# LM_001.net
KiCad netlist of a schematic drawn in Altium Designer
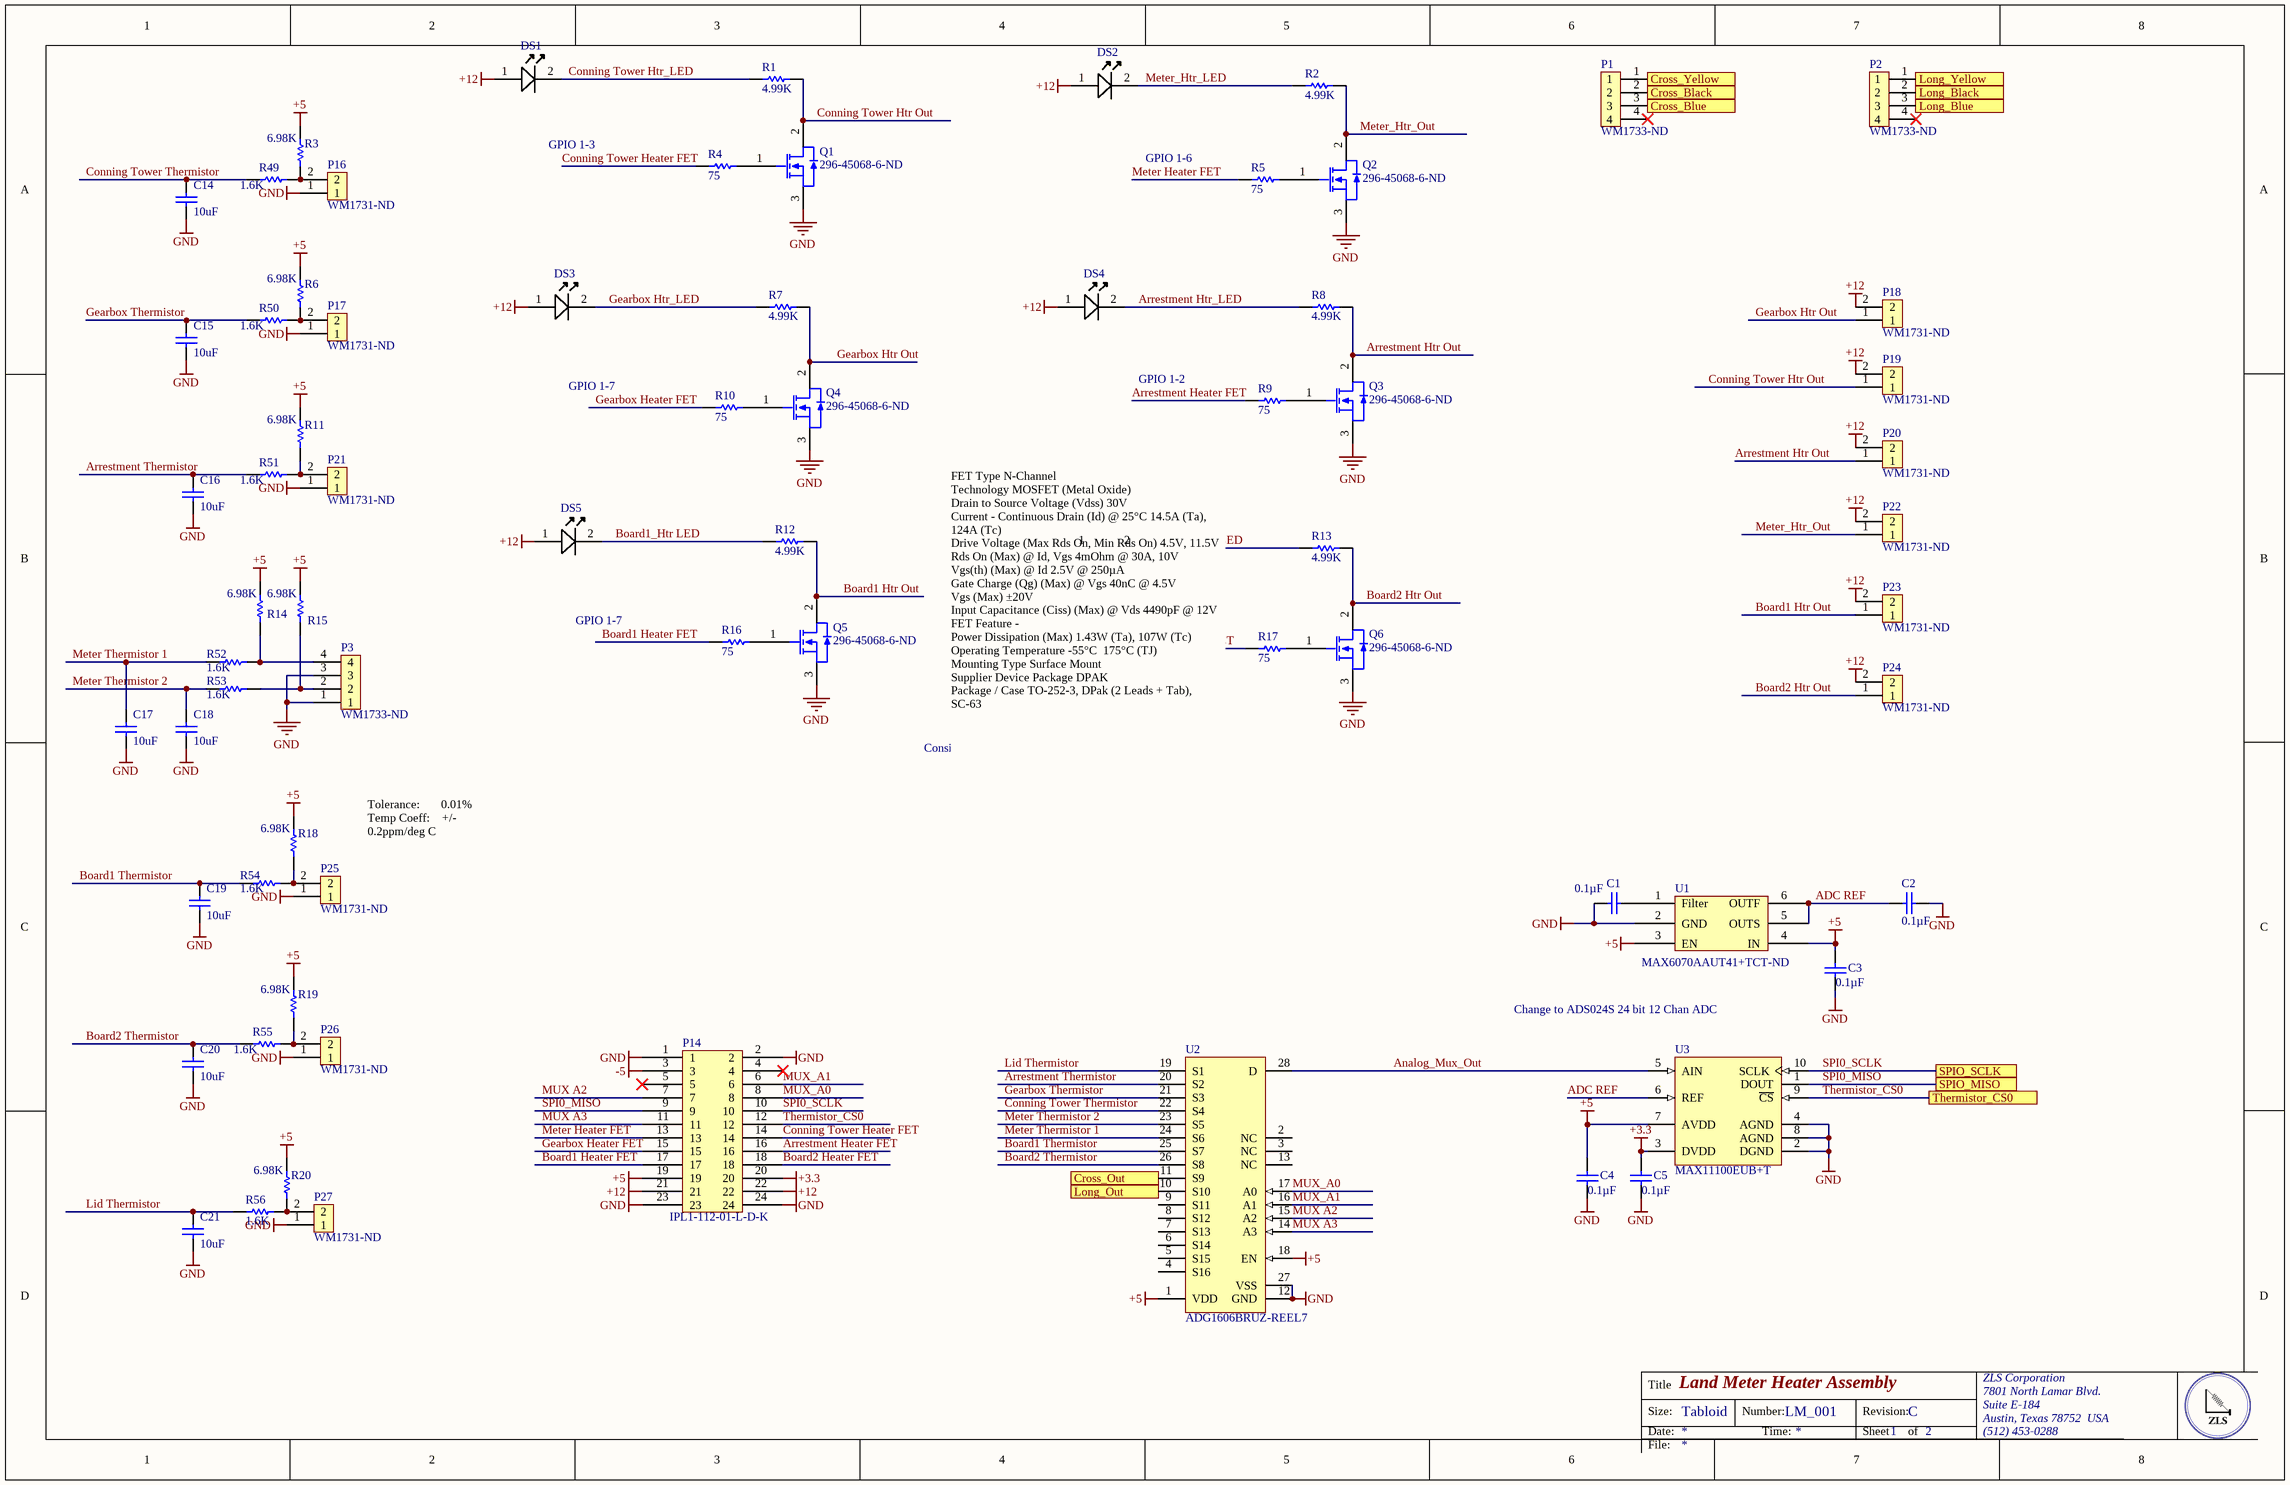
[diagram p0: LM_001.SchDoc]

(export (version "E")
  (design (tool "Eeschema 10.0.6"))
  (components
    (comp (ref "C1")
      (value "CAP CER 0.1UF 25V X7R 0805")
      (footprint "CAPC0805(2012)145_N")
      (fields
        (field (name "MANUFACTURER") "Murata Electronics North America")
        (field (name "MANUFACTURER PART NUMBER") "GRM21BR71E104KA01L")
        (field (name "CAPACITANCE") "0.1µF")
        (field (name "TOLERANCE") "±10%")
      )
      (libsource (lib "Altium Content Vault") (part "CMP-1036-04795-1"))
    )
    (comp (ref "C2")
      (value "CAP CER 0.1UF 25V X7R 0805")
      (footprint "CAPC0805(2012)145_N")
      (fields
        (field (name "MANUFACTURER") "Murata Electronics North America")
        (field (name "MANUFACTURER PART NUMBER") "GRM21BR71E104KA01L")
        (field (name "CAPACITANCE") "0.1µF")
        (field (name "TOLERANCE") "±10%")
      )
      (libsource (lib "Altium Content Vault") (part "CMP-1036-04795-1"))
    )
    (comp (ref "C3")
      (value "CAP CER 0.1UF 25V X7R 0805")
      (footprint "CAPC0805(2012)145_N")
      (fields
        (field (name "MANUFACTURER") "Murata Electronics North America")
        (field (name "MANUFACTURER PART NUMBER") "GRM21BR71E104KA01L")
        (field (name "CAPACITANCE") "0.1µF")
        (field (name "TOLERANCE") "±10%")
      )
      (libsource (lib "Altium Content Vault") (part "CMP-1036-04795-1"))
    )
    (comp (ref "C4")
      (value "CAP CER 0.1UF 25V X7R 0805")
      (footprint "CAPC0805(2012)145_N")
      (fields
        (field (name "MANUFACTURER") "Murata Electronics North America")
        (field (name "MANUFACTURER PART NUMBER") "GRM21BR71E104KA01L")
        (field (name "CAPACITANCE") "0.1µF")
        (field (name "TOLERANCE") "±10%")
      )
      (libsource (lib "Altium Content Vault") (part "CMP-1036-04795-1"))
    )
    (comp (ref "C5")
      (value "CAP CER 0.1UF 25V X7R 0805")
      (footprint "CAPC0805(2012)145_N")
      (fields
        (field (name "MANUFACTURER") "Murata Electronics North America")
        (field (name "MANUFACTURER PART NUMBER") "GRM21BR71E104KA01L")
        (field (name "CAPACITANCE") "0.1µF")
        (field (name "TOLERANCE") "±10%")
      )
      (libsource (lib "Altium Content Vault") (part "CMP-1036-04795-1"))
    )
    (comp (ref "C14")
      (value "10uF")
      (footprint "CAPC0805(2012)145_N")
      (description "CAP CER 10UF 16V X6S 0805")
      (fields
        (field (name "MANUFACTURER") "TDK Corporation")
        (field (name "MANUFACTURER PART NUMBER") "C2012X6S1C106K085AC")
      )
      (libsource (lib "Altium Content Vault") (part "CMP-1036-04795-1"))
    )
    (comp (ref "C15")
      (value "10uF")
      (footprint "CAPC0805(2012)145_N")
      (description "CAP CER 10UF 16V X6S 0805")
      (fields
        (field (name "MANUFACTURER") "TDK Corporation")
        (field (name "MANUFACTURER PART NUMBER") "C2012X6S1C106K085AC")
      )
      (libsource (lib "Altium Content Vault") (part "CMP-1036-04795-1"))
    )
    (comp (ref "C16")
      (value "10uF")
      (footprint "CAPC0805(2012)145_N")
      (description "CAP CER 10UF 16V X6S 0805")
      (fields
        (field (name "MANUFACTURER") "TDK Corporation")
        (field (name "MANUFACTURER PART NUMBER") "C2012X6S1C106K085AC")
      )
      (libsource (lib "Altium Content Vault") (part "CMP-1036-04795-1"))
    )
    (comp (ref "C17")
      (value "10uF")
      (footprint "CAPC0805(2012)145_N")
      (description "CAP CER 10UF 16V X6S 0805")
      (fields
        (field (name "MANUFACTURER") "TDK Corporation")
        (field (name "MANUFACTURER PART NUMBER") "C2012X6S1C106K085AC")
      )
      (libsource (lib "Altium Content Vault") (part "CMP-1036-04795-1"))
    )
    (comp (ref "C18")
      (value "10uF")
      (footprint "CAPC0805(2012)145_N")
      (description "CAP CER 10UF 16V X6S 0805")
      (fields
        (field (name "MANUFACTURER") "TDK Corporation")
        (field (name "MANUFACTURER PART NUMBER") "C2012X6S1C106K085AC")
      )
      (libsource (lib "Altium Content Vault") (part "CMP-1036-04795-1"))
    )
    (comp (ref "C19")
      (value "10uF")
      (footprint "CAPC0805(2012)145_N")
      (description "CAP CER 10UF 16V X6S 0805")
      (fields
        (field (name "MANUFACTURER") "TDK Corporation")
        (field (name "MANUFACTURER PART NUMBER") "C2012X6S1C106K085AC")
      )
      (libsource (lib "Altium Content Vault") (part "CMP-1036-04795-1"))
    )
    (comp (ref "C20")
      (value "10uF")
      (footprint "CAPC0805(2012)145_N")
      (description "CAP CER 10UF 16V X6S 0805")
      (fields
        (field (name "MANUFACTURER") "TDK Corporation")
        (field (name "MANUFACTURER PART NUMBER") "C2012X6S1C106K085AC")
      )
      (libsource (lib "Altium Content Vault") (part "CMP-1036-04795-1"))
    )
    (comp (ref "C21")
      (value "10uF")
      (footprint "CAPC0805(2012)145_N")
      (description "CAP CER 10UF 16V X6S 0805")
      (fields
        (field (name "MANUFACTURER") "TDK Corporation")
        (field (name "MANUFACTURER PART NUMBER") "C2012X6S1C106K085AC")
      )
      (libsource (lib "Altium Content Vault") (part "CMP-1036-04795-1"))
    )
    (comp (ref "DS1")
      (value "LTST-S220KRKT")
      (footprint "0805C_L")
      (description "LED RED CLEAR CHIP SMD R/A")
      (fields (field (name "MANUFACTURER") "Vishay / Lite-On"))
      (libsource (lib "*") (part "LED A/K"))
    )
    (comp (ref "DS2")
      (value "LTST-S220KRKT")
      (footprint "0805C_L")
      (description "LED RED CLEAR CHIP SMD R/A")
      (fields (field (name "MANUFACTURER") "Vishay / Lite-On"))
      (libsource (lib "*") (part "LED A/K"))
    )
    (comp (ref "DS3")
      (value "LTST-S220KRKT")
      (footprint "0805C_L")
      (description "LED RED CLEAR CHIP SMD R/A")
      (fields (field (name "MANUFACTURER") "Vishay / Lite-On"))
      (libsource (lib "*") (part "LED A/K"))
    )
    (comp (ref "DS4")
      (value "LTST-S220KRKT")
      (footprint "0805C_L")
      (description "LED RED CLEAR CHIP SMD R/A")
      (fields (field (name "MANUFACTURER") "Vishay / Lite-On"))
      (libsource (lib "*") (part "LED A/K"))
    )
    (comp (ref "DS5")
      (value "LTST-S220KRKT")
      (footprint "0805C_L")
      (description "LED RED CLEAR CHIP SMD R/A")
      (fields (field (name "MANUFACTURER") "Vishay / Lite-On"))
      (libsource (lib "*") (part "LED A/K"))
    )
    (comp (ref "DS6")
      (value "LTST-S220KRKT")
      (footprint "0805C_L")
      (description "LED RED CLEAR CHIP SMD R/A")
      (fields (field (name "MANUFACTURER") "Vishay / Lite-On"))
      (libsource (lib "*") (part "LED A/K"))
    )
    (comp (ref "P1")
      (value "0530470410")
      (footprint "0530470410")
      (description "Conn Wire to Board HDR 4 POS 1.25mm Solder ST Thru-Hole PicoBlade™ Tray")
      (fields (field (name "SUPPLIER PART NUMBER 1") "WM1733-ND") (field (name "MANUFACTURER") "Molex"))
      (libsource (lib "ZLS_Schematic_lib") (part "0530470410"))
    )
    (comp (ref "P2")
      (value "0530470410")
      (footprint "0530470410")
      (description "Conn Wire to Board HDR 4 POS 1.25mm Solder ST Thru-Hole PicoBlade™ Tray")
      (fields (field (name "SUPPLIER PART NUMBER 1") "WM1733-ND") (field (name "MANUFACTURER") "Molex"))
      (libsource (lib "ZLS_Schematic_lib") (part "0530470410"))
    )
    (comp (ref "P3")
      (value "0530470410")
      (footprint "0530470410")
      (description "Conn Wire to Board HDR 4 POS 1.25mm Solder ST Thru-Hole PicoBlade™ Tray")
      (fields (field (name "SUPPLIER PART NUMBER 1") "WM1733-ND") (field (name "MANUFACTURER") "Molex"))
      (libsource (lib "") (part "0530470410_1"))
    )
    (comp (ref "P14")
      (value "IPL1-112-01-L-D-K")
      (footprint "IPL1-112-01-F-S-K")
      (fields (field (name "MANUFACTURER") "Samtec Inc."))
      (libsource (lib "ZLS_Schematic_lib") (part "IPL1-112-01-F-S-K"))
    )
    (comp (ref "P16")
      (value "0530470210")
      (footprint "0530470210")
      (description "Conn Shrouded Header HDR 2 POS 1.25mm Solder ST Thru-Hole PicoBlade™ Tray")
      (fields (field (name "SUPPLIER PART NUMBER 1") "WM1731-ND") (field (name "MANUFACTURER") "Molex"))
      (libsource (lib "ZLS_Schematic_lib") (part "0530470210"))
    )
    (comp (ref "P17")
      (value "0530470210")
      (footprint "0530470210")
      (description "Conn Shrouded Header HDR 2 POS 1.25mm Solder ST Thru-Hole PicoBlade™ Tray")
      (fields (field (name "SUPPLIER PART NUMBER 1") "WM1731-ND") (field (name "MANUFACTURER") "Molex"))
      (libsource (lib "ZLS_Schematic_lib") (part "0530470210"))
    )
    (comp (ref "P18")
      (value "0530470210")
      (footprint "0530470210")
      (description "Conn Shrouded Header HDR 2 POS 1.25mm Solder ST Thru-Hole PicoBlade™ Tray")
      (fields (field (name "SUPPLIER PART NUMBER 1") "WM1731-ND") (field (name "MANUFACTURER") "Molex"))
      (libsource (lib "ZLS_Schematic_lib") (part "0530470210"))
    )
    (comp (ref "P19")
      (value "0530470210")
      (footprint "0530470210")
      (description "Conn Shrouded Header HDR 2 POS 1.25mm Solder ST Thru-Hole PicoBlade™ Tray")
      (fields (field (name "SUPPLIER PART NUMBER 1") "WM1731-ND") (field (name "MANUFACTURER") "Molex"))
      (libsource (lib "ZLS_Schematic_lib") (part "0530470210"))
    )
    (comp (ref "P20")
      (value "0530470210")
      (footprint "0530470210")
      (description "Conn Shrouded Header HDR 2 POS 1.25mm Solder ST Thru-Hole PicoBlade™ Tray")
      (fields (field (name "SUPPLIER PART NUMBER 1") "WM1731-ND") (field (name "MANUFACTURER") "Molex"))
      (libsource (lib "ZLS_Schematic_lib") (part "0530470210"))
    )
    (comp (ref "P21")
      (value "0530470210")
      (footprint "0530470210")
      (description "Conn Shrouded Header HDR 2 POS 1.25mm Solder ST Thru-Hole PicoBlade™ Tray")
      (fields (field (name "SUPPLIER PART NUMBER 1") "WM1731-ND") (field (name "MANUFACTURER") "Molex"))
      (libsource (lib "ZLS_Schematic_lib") (part "0530470210"))
    )
    (comp (ref "P22")
      (value "0530470210")
      (footprint "0530470210")
      (description "Conn Shrouded Header HDR 2 POS 1.25mm Solder ST Thru-Hole PicoBlade™ Tray")
      (fields (field (name "SUPPLIER PART NUMBER 1") "WM1731-ND") (field (name "MANUFACTURER") "Molex"))
      (libsource (lib "ZLS_Schematic_lib") (part "0530470210"))
    )
    (comp (ref "P23")
      (value "0530470210")
      (footprint "0530470210")
      (description "Conn Shrouded Header HDR 2 POS 1.25mm Solder ST Thru-Hole PicoBlade™ Tray")
      (fields (field (name "SUPPLIER PART NUMBER 1") "WM1731-ND") (field (name "MANUFACTURER") "Molex"))
      (libsource (lib "ZLS_Schematic_lib") (part "0530470210"))
    )
    (comp (ref "P24")
      (value "0530470210")
      (footprint "0530470210")
      (description "Conn Shrouded Header HDR 2 POS 1.25mm Solder ST Thru-Hole PicoBlade™ Tray")
      (fields (field (name "SUPPLIER PART NUMBER 1") "WM1731-ND") (field (name "MANUFACTURER") "Molex"))
      (libsource (lib "ZLS_Schematic_lib") (part "0530470210"))
    )
    (comp (ref "P25")
      (value "0530470210")
      (footprint "0530470210")
      (description "Conn Shrouded Header HDR 2 POS 1.25mm Solder ST Thru-Hole PicoBlade™ Tray")
      (fields (field (name "SUPPLIER PART NUMBER 1") "WM1731-ND") (field (name "MANUFACTURER") "Molex"))
      (libsource (lib "ZLS_Schematic_lib") (part "0530470210"))
    )
    (comp (ref "P26")
      (value "0530470210")
      (footprint "0530470210")
      (description "Conn Shrouded Header HDR 2 POS 1.25mm Solder ST Thru-Hole PicoBlade™ Tray")
      (fields (field (name "SUPPLIER PART NUMBER 1") "WM1731-ND") (field (name "MANUFACTURER") "Molex"))
      (libsource (lib "ZLS_Schematic_lib") (part "0530470210"))
    )
    (comp (ref "P27")
      (value "0530470210")
      (footprint "0530470210")
      (description "Conn Shrouded Header HDR 2 POS 1.25mm Solder ST Thru-Hole PicoBlade™ Tray")
      (fields (field (name "SUPPLIER PART NUMBER 1") "WM1731-ND") (field (name "MANUFACTURER") "Molex"))
      (libsource (lib "ZLS_Schematic_lib") (part "0530470210"))
    )
    (comp (ref "Q1")
      (value "CSD17585F5T")
      (footprint "CSD17585F5T")
      (description "MOSFET N-CH 30V 5.9A PICOSTAR")
      (fields (field (name "SUPPLIER PART NUMBER 1") "296-45068-6-ND"))
      (libsource (lib "ZLS_Schematic_lib") (part "CSD17585F5T"))
    )
    (comp (ref "Q2")
      (value "CSD17585F5T")
      (footprint "CSD17585F5T")
      (description "MOSFET N-CH 30V 5.9A PICOSTAR")
      (fields (field (name "SUPPLIER PART NUMBER 1") "296-45068-6-ND"))
      (libsource (lib "ZLS_Schematic_lib") (part "CSD17585F5T"))
    )
    (comp (ref "Q3")
      (value "CSD17585F5T")
      (footprint "CSD17585F5T")
      (description "MOSFET N-CH 30V 5.9A PICOSTAR")
      (fields (field (name "SUPPLIER PART NUMBER 1") "296-45068-6-ND"))
      (libsource (lib "ZLS_Schematic_lib") (part "CSD17585F5T"))
    )
    (comp (ref "Q4")
      (value "CSD17585F5T")
      (footprint "CSD17585F5T")
      (description "MOSFET N-CH 30V 5.9A PICOSTAR")
      (fields (field (name "SUPPLIER PART NUMBER 1") "296-45068-6-ND"))
      (libsource (lib "ZLS_Schematic_lib") (part "CSD17585F5T"))
    )
    (comp (ref "Q5")
      (value "CSD17585F5T")
      (footprint "CSD17585F5T")
      (description "MOSFET N-CH 30V 5.9A PICOSTAR")
      (fields (field (name "SUPPLIER PART NUMBER 1") "296-45068-6-ND"))
      (libsource (lib "ZLS_Schematic_lib") (part "CSD17585F5T"))
    )
    (comp (ref "Q6")
      (value "CSD17585F5T")
      (footprint "CSD17585F5T")
      (description "MOSFET N-CH 30V 5.9A PICOSTAR")
      (fields (field (name "SUPPLIER PART NUMBER 1") "296-45068-6-ND"))
      (libsource (lib "ZLS_Schematic_lib") (part "CSD17585F5T"))
    )
    (comp (ref "R1")
      (value "4.99K")
      (footprint "RESC0805(2012)_L")
      (description "RES SMD 4.99K OHM 1% 1/8W 0805")
      (fields
        (field (name "MANUFACTURER") "Vishay Dale")
        (field (name "MANUFACTURER PART NUMBER") "CRCW08054K99FKEA")
      )
      (libsource (lib "Altium Content Vault") (part "CMP-1013-00393-1"))
    )
    (comp (ref "R2")
      (value "4.99K")
      (footprint "RESC0805(2012)_L")
      (description "RES SMD 4.99K OHM 1% 1/8W 0805")
      (fields
        (field (name "MANUFACTURER") "Vishay Dale")
        (field (name "MANUFACTURER PART NUMBER") "CRCW08054K99FKEA")
      )
      (libsource (lib "Altium Content Vault") (part "CMP-1013-00393-1"))
    )
    (comp (ref "R3")
      (value "6.98K")
      (footprint "RESC0805(2012)_N")
      (description "RES SMD 6.98K OHM 1% 1/8W 0805")
      (fields
        (field (name "MANUFACTURER") "Vishay Dale")
        (field (name "MANUFACTURER PART NUMBER") "CRCW08056K98FKEA")
      )
      (libsource (lib "Altium Content Vault") (part "CMP-1013-00606-1"))
    )
    (comp (ref "R4")
      (value "75")
      (footprint "RESC0805(2012)_L")
      (description "RES SMD 75 OHM 1% 1/8W 0805")
      (fields
        (field (name "MANUFACTURER") "Vishay Dale")
        (field (name "MANUFACTURER PART NUMBER") "CRCW080575R0FKTA")
      )
      (libsource (lib "Altium Content Vault") (part "CMP-1013-00393-1"))
    )
    (comp (ref "R5")
      (value "75")
      (footprint "RESC0805(2012)_L")
      (description "RES SMD 75 OHM 1% 1/8W 0805")
      (fields
        (field (name "MANUFACTURER") "Vishay Dale")
        (field (name "MANUFACTURER PART NUMBER") "CRCW080575R0FKTA")
      )
      (libsource (lib "Altium Content Vault") (part "CMP-1013-00393-1"))
    )
    (comp (ref "R6")
      (value "6.98K")
      (footprint "RESC0805(2012)_N")
      (description "RES SMD 6.98K OHM 1% 1/8W 0805")
      (fields
        (field (name "MANUFACTURER") "Vishay Dale")
        (field (name "MANUFACTURER PART NUMBER") "CRCW08056K98FKEA")
      )
      (libsource (lib "Altium Content Vault") (part "CMP-1013-00606-1"))
    )
    (comp (ref "R7")
      (value "4.99K")
      (footprint "RESC0805(2012)_L")
      (description "RES SMD 4.99K OHM 1% 1/8W 0805")
      (fields
        (field (name "MANUFACTURER") "Vishay Dale")
        (field (name "MANUFACTURER PART NUMBER") "CRCW08054K99FKEA")
      )
      (libsource (lib "Altium Content Vault") (part "CMP-1013-00393-1"))
    )
    (comp (ref "R8")
      (value "4.99K")
      (footprint "RESC0805(2012)_L")
      (description "RES SMD 4.99K OHM 1% 1/8W 0805")
      (fields
        (field (name "MANUFACTURER") "Vishay Dale")
        (field (name "MANUFACTURER PART NUMBER") "CRCW08054K99FKEA")
      )
      (libsource (lib "Altium Content Vault") (part "CMP-1013-00393-1"))
    )
    (comp (ref "R9")
      (value "75")
      (footprint "RESC0805(2012)_L")
      (description "RES SMD 75 OHM 1% 1/8W 0805")
      (fields
        (field (name "MANUFACTURER") "Vishay Dale")
        (field (name "MANUFACTURER PART NUMBER") "CRCW080575R0FKTA")
      )
      (libsource (lib "Altium Content Vault") (part "CMP-1013-00393-1"))
    )
    (comp (ref "R10")
      (value "75")
      (footprint "RESC0805(2012)_L")
      (description "RES SMD 75 OHM 1% 1/8W 0805")
      (fields
        (field (name "MANUFACTURER") "Vishay Dale")
        (field (name "MANUFACTURER PART NUMBER") "CRCW080575R0FKTA")
      )
      (libsource (lib "Altium Content Vault") (part "CMP-1013-00393-1"))
    )
    (comp (ref "R11")
      (value "6.98K")
      (footprint "RESC0805(2012)_N")
      (description "RES SMD 6.98K OHM 1% 1/8W 0805")
      (fields
        (field (name "MANUFACTURER") "Vishay Dale")
        (field (name "MANUFACTURER PART NUMBER") "CRCW08056K98FKEA")
      )
      (libsource (lib "Altium Content Vault") (part "CMP-1013-00606-1"))
    )
    (comp (ref "R12")
      (value "4.99K")
      (footprint "RESC0805(2012)_L")
      (description "RES SMD 4.99K OHM 1% 1/8W 0805")
      (fields
        (field (name "MANUFACTURER") "Vishay Dale")
        (field (name "MANUFACTURER PART NUMBER") "CRCW08054K99FKEA")
      )
      (libsource (lib "Altium Content Vault") (part "CMP-1013-00393-1"))
    )
    (comp (ref "R13")
      (value "4.99K")
      (footprint "RESC0805(2012)_L")
      (description "RES SMD 4.99K OHM 1% 1/8W 0805")
      (fields
        (field (name "MANUFACTURER") "Vishay Dale")
        (field (name "MANUFACTURER PART NUMBER") "CRCW08054K99FKEA")
      )
      (libsource (lib "Altium Content Vault") (part "CMP-1013-00393-1"))
    )
    (comp (ref "R14")
      (value "6.98K")
      (footprint "RESC0805(2012)_N")
      (description "RES SMD 6.98K OHM 1% 1/8W 0805")
      (fields
        (field (name "MANUFACTURER") "Vishay Dale")
        (field (name "MANUFACTURER PART NUMBER") "CRCW08056K98FKEA")
      )
      (libsource (lib "Altium Content Vault") (part "CMP-1013-00606-1"))
    )
    (comp (ref "R15")
      (value "6.98K")
      (footprint "RESC0805(2012)_N")
      (description "RES SMD 6.98K OHM 1% 1/8W 0805")
      (fields
        (field (name "MANUFACTURER") "Vishay Dale")
        (field (name "MANUFACTURER PART NUMBER") "CRCW08056K98FKEA")
      )
      (libsource (lib "Altium Content Vault") (part "CMP-1013-00606-1"))
    )
    (comp (ref "R16")
      (value "75")
      (footprint "RESC0805(2012)_L")
      (description "RES SMD 75 OHM 1% 1/8W 0805")
      (fields
        (field (name "MANUFACTURER") "Vishay Dale")
        (field (name "MANUFACTURER PART NUMBER") "CRCW080575R0FKTA")
      )
      (libsource (lib "Altium Content Vault") (part "CMP-1013-00393-1"))
    )
    (comp (ref "R17")
      (value "75")
      (footprint "RESC0805(2012)_L")
      (description "RES SMD 75 OHM 1% 1/8W 0805")
      (fields
        (field (name "MANUFACTURER") "Vishay Dale")
        (field (name "MANUFACTURER PART NUMBER") "CRCW080575R0FKTA")
      )
      (libsource (lib "Altium Content Vault") (part "CMP-1013-00393-1"))
    )
    (comp (ref "R18")
      (value "6.98K")
      (footprint "RESC0805(2012)_N")
      (description "RES SMD 6.98K OHM 1% 1/8W 0805")
      (fields
        (field (name "MANUFACTURER") "Vishay Dale")
        (field (name "MANUFACTURER PART NUMBER") "CRCW08056K98FKEA")
      )
      (libsource (lib "Altium Content Vault") (part "CMP-1013-00606-1"))
    )
    (comp (ref "R19")
      (value "6.98K")
      (footprint "RESC0805(2012)_N")
      (description "RES SMD 6.98K OHM 1% 1/8W 0805")
      (fields
        (field (name "MANUFACTURER") "Vishay Dale")
        (field (name "MANUFACTURER PART NUMBER") "CRCW08056K98FKEA")
      )
      (libsource (lib "Altium Content Vault") (part "CMP-1013-00606-1"))
    )
    (comp (ref "R20")
      (value "6.98K")
      (footprint "RESC0805(2012)_N")
      (description "RES SMD 6.98K OHM 1% 1/8W 0805")
      (fields
        (field (name "MANUFACTURER") "Vishay Dale")
        (field (name "MANUFACTURER PART NUMBER") "CRCW08056K98FKEA")
      )
      (libsource (lib "Altium Content Vault") (part "CMP-1013-00606-1"))
    )
    (comp (ref "R49")
      (value "1.6K")
      (footprint "RESC0805(2012)_N")
      (description "RES SMD 1.6K OHM 1% 1/8W 0805")
      (libsource (lib "Altium Content Vault") (part "CMP-1013-00606-1"))
    )
    (comp (ref "R50")
      (value "1.6K")
      (footprint "RESC0805(2012)_N")
      (description "RES SMD 1.6K OHM 1% 1/8W 0805")
      (libsource (lib "Altium Content Vault") (part "CMP-1013-00606-1"))
    )
    (comp (ref "R51")
      (value "1.6K")
      (footprint "RESC0805(2012)_N")
      (description "RES SMD 1.6K OHM 1% 1/8W 0805")
      (libsource (lib "Altium Content Vault") (part "CMP-1013-00606-1"))
    )
    (comp (ref "R52")
      (value "1.6K")
      (footprint "RESC0805(2012)_N")
      (description "RES SMD 1.6K OHM 1% 1/8W 0805")
      (libsource (lib "Altium Content Vault") (part "CMP-1013-00606-1"))
    )
    (comp (ref "R53")
      (value "1.6K")
      (footprint "RESC0805(2012)_N")
      (description "RES SMD 1.6K OHM 1% 1/8W 0805")
      (libsource (lib "Altium Content Vault") (part "CMP-1013-00606-1"))
    )
    (comp (ref "R54")
      (value "1.6K")
      (footprint "RESC0805(2012)_N")
      (description "RES SMD 1.6K OHM 1% 1/8W 0805")
      (libsource (lib "Altium Content Vault") (part "CMP-1013-00606-1"))
    )
    (comp (ref "R55")
      (value "1.6K")
      (footprint "RESC0805(2012)_N")
      (description "RES SMD 1.6K OHM 1% 1/8W 0805")
      (libsource (lib "Altium Content Vault") (part "CMP-1013-00606-1"))
    )
    (comp (ref "R56")
      (value "1.6K")
      (footprint "RESC0805(2012)_N")
      (description "RES SMD 1.6K OHM 1% 1/8W 0805")
      (libsource (lib "Altium Content Vault") (part "CMP-1013-00606-1"))
    )
    (comp (ref "U1")
      (value "MAX6070AAUT41+T")
      (footprint "SOT95P280X445-6N")
      (description "IC VREF SERIES 4.096V SOT23")
      (fields
        (field (name "SUPPLIER PART NUMBER 1") "MAX6070AAUT41+TCT-ND")
        (field (name "MANUFACTURER") "Maxim Integrated")
        (field (name "TOLERANCE") "±0.04%")
      )
      (libsource (lib "ZLS_Schematic_lib") (part "MAX6070AAUT41+T"))
    )
    (comp (ref "U2")
      (value "ADG1606BRUZ-REEL7")
      (footprint "ADI-RU-28_M")
      (description "4.5 Ohm Ron, 16-Channel, +/-5 V,+12 V,+5 V and +3.3 V Multiplexer, 28-pin SOP (RU-28), Reel")
      (fields (field (name "MANUFACTURER") "Analog Devices"))
      (libsource (lib "Altium Content Vault") (part "ADI-ADG1606-RU-28"))
    )
    (comp (ref "U3")
      (value "MAX11100EUB+T")
      (footprint "U10+2_L")
      (description "16-Bit, +5V, 200ksps ADC with 10uA Shutdown, 10-Pin uMAX, -40°C to +85°C, Pb-Free, Tape and Reel")
      (libsource (lib "Altium Content Vault") (part "CON-ADC-MAX11100-IL10"))
    )
  )
  (nets
    (net (code "1") (name "+3.3") (class "Default")
      (node (ref "C5") (pin "1") (pinfunction "1_1") (pintype "passive"))
      (node (ref "P14") (pin "20") (pinfunction "20_20") (pintype "passive"))
      (node (ref "U3") (pin "3") (pinfunction "DVDD_3") (pintype "power_in"))
    )
    (net (code "2") (name "+5") (class "Default")
      (node (ref "C3") (pin "1") (pinfunction "1_1") (pintype "passive"))
      (node (ref "C4") (pin "1") (pinfunction "1_1") (pintype "passive"))
      (node (ref "P14") (pin "19") (pinfunction "19_19") (pintype "passive"))
      (node (ref "R11") (pin "2") (pinfunction "2_2") (pintype "passive"))
      (node (ref "R14") (pin "2") (pinfunction "2_2") (pintype "passive"))
      (node (ref "R15") (pin "2") (pinfunction "2_2") (pintype "passive"))
      (node (ref "R18") (pin "2") (pinfunction "2_2") (pintype "passive"))
      (node (ref "R19") (pin "2") (pinfunction "2_2") (pintype "passive"))
      (node (ref "R20") (pin "2") (pinfunction "2_2") (pintype "passive"))
      (node (ref "R3") (pin "2") (pinfunction "2_2") (pintype "passive"))
      (node (ref "R6") (pin "2") (pinfunction "2_2") (pintype "passive"))
      (node (ref "U1") (pin "3") (pinfunction "EN_3") (pintype "passive"))
      (node (ref "U1") (pin "4") (pinfunction "IN_4") (pintype "passive"))
      (node (ref "U2") (pin "1") (pinfunction "VDD_1") (pintype "power_in"))
      (node (ref "U2") (pin "18") (pinfunction "EN_18") (pintype "input"))
      (node (ref "U3") (pin "7") (pinfunction "AVDD_7") (pintype "power_in"))
    )
    (net (code "3") (name "+12") (class "Default")
      (node (ref "DS1") (pin "1") (pinfunction "A_1") (pintype "passive"))
      (node (ref "DS2") (pin "1") (pinfunction "A_1") (pintype "passive"))
      (node (ref "DS3") (pin "1") (pinfunction "A_1") (pintype "passive"))
      (node (ref "DS4") (pin "1") (pinfunction "A_1") (pintype "passive"))
      (node (ref "DS5") (pin "1") (pinfunction "A_1") (pintype "passive"))
      (node (ref "DS6") (pin "1") (pinfunction "A_1") (pintype "passive"))
      (node (ref "P14") (pin "21") (pinfunction "21_21") (pintype "passive"))
      (node (ref "P14") (pin "22") (pinfunction "22_22") (pintype "passive"))
      (node (ref "P18") (pin "2") (pinfunction "2_2") (pintype "passive"))
      (node (ref "P19") (pin "2") (pinfunction "2_2") (pintype "passive"))
      (node (ref "P20") (pin "2") (pinfunction "2_2") (pintype "passive"))
      (node (ref "P22") (pin "2") (pinfunction "2_2") (pintype "passive"))
      (node (ref "P23") (pin "2") (pinfunction "2_2") (pintype "passive"))
      (node (ref "P24") (pin "2") (pinfunction "2_2") (pintype "passive"))
    )
    (net (code "4") (name "-5") (class "Default")
      (node (ref "P14") (pin "3") (pinfunction "3_3") (pintype "passive"))
    )
    (net (code "5") (name "/ADC REF") (class "Default")
      (node (ref "C2") (pin "1") (pinfunction "1_1") (pintype "passive"))
      (node (ref "U1") (pin "5") (pinfunction "OUTS_5") (pintype "passive"))
      (node (ref "U1") (pin "6") (pinfunction "OUTF_6") (pintype "passive"))
      (node (ref "U3") (pin "6") (pinfunction "REF_6") (pintype "input"))
    )
    (net (code "6") (name "/Analog_Mux_Out") (class "Default")
      (node (ref "U2") (pin "28") (pinfunction "D_28") (pintype "passive"))
      (node (ref "U3") (pin "5") (pinfunction "AIN_5") (pintype "input"))
    )
    (net (code "7") (name "/Arrestment Heater FET") (class "Default")
      (node (ref "P14") (pin "16") (pinfunction "16_16") (pintype "passive"))
      (node (ref "R9") (pin "1") (pinfunction "1_1") (pintype "passive"))
    )
    (net (code "8") (name "/Arrestment Htr Out") (class "Default")
      (node (ref "P20") (pin "1") (pinfunction "1_1") (pintype "passive"))
      (node (ref "Q3") (pin "2") (pinfunction "D_2") (pintype "passive"))
      (node (ref "R8") (pin "1") (pinfunction "1_1") (pintype "passive"))
    )
    (net (code "9") (name "/Arrestment Htr_LED") (class "Default")
      (node (ref "DS4") (pin "2") (pinfunction "K_2") (pintype "passive"))
      (node (ref "R8") (pin "2") (pinfunction "2_2") (pintype "passive"))
    )
    (net (code "10") (name "/Arrestment Thermistor") (class "Default")
      (node (ref "C16") (pin "1") (pinfunction "1_1") (pintype "passive"))
      (node (ref "R51") (pin "2") (pinfunction "2_2") (pintype "passive"))
      (node (ref "U2") (pin "20") (pinfunction "S2_20") (pintype "passive"))
    )
    (net (code "11") (name "/Board1 Heater FET") (class "Default")
      (node (ref "P14") (pin "17") (pinfunction "17_17") (pintype "passive"))
      (node (ref "R16") (pin "1") (pinfunction "1_1") (pintype "passive"))
    )
    (net (code "12") (name "/Board1 Htr Out") (class "Default")
      (node (ref "P23") (pin "1") (pinfunction "1_1") (pintype "passive"))
      (node (ref "Q5") (pin "2") (pinfunction "D_2") (pintype "passive"))
      (node (ref "R12") (pin "1") (pinfunction "1_1") (pintype "passive"))
    )
    (net (code "13") (name "/Board1 Thermistor") (class "Default")
      (node (ref "C19") (pin "1") (pinfunction "1_1") (pintype "passive"))
      (node (ref "R54") (pin "2") (pinfunction "2_2") (pintype "passive"))
      (node (ref "U2") (pin "25") (pinfunction "S7_25") (pintype "passive"))
    )
    (net (code "14") (name "/Board1_Htr LED") (class "Default")
      (node (ref "DS5") (pin "2") (pinfunction "K_2") (pintype "passive"))
      (node (ref "R12") (pin "2") (pinfunction "2_2") (pintype "passive"))
    )
    (net (code "15") (name "/Board2 Heater FET") (class "Default")
      (node (ref "P14") (pin "18") (pinfunction "18_18") (pintype "passive"))
      (node (ref "R17") (pin "1") (pinfunction "1_1") (pintype "passive"))
    )
    (net (code "16") (name "/Board2 Htr Out") (class "Default")
      (node (ref "P24") (pin "1") (pinfunction "1_1") (pintype "passive"))
      (node (ref "Q6") (pin "2") (pinfunction "D_2") (pintype "passive"))
      (node (ref "R13") (pin "1") (pinfunction "1_1") (pintype "passive"))
    )
    (net (code "17") (name "/Board2 Thermistor") (class "Default")
      (node (ref "C20") (pin "1") (pinfunction "1_1") (pintype "passive"))
      (node (ref "R55") (pin "2") (pinfunction "2_2") (pintype "passive"))
      (node (ref "U2") (pin "26") (pinfunction "S8_26") (pintype "passive"))
    )
    (net (code "18") (name "/Board2_Htr LED") (class "Default")
      (node (ref "DS6") (pin "2") (pinfunction "K_2") (pintype "passive"))
      (node (ref "R13") (pin "2") (pinfunction "2_2") (pintype "passive"))
    )
    (net (code "19") (name "/Conning Tower Heater FET") (class "Default")
      (node (ref "P14") (pin "14") (pinfunction "14_14") (pintype "passive"))
      (node (ref "R4") (pin "1") (pinfunction "1_1") (pintype "passive"))
    )
    (net (code "20") (name "/Conning Tower Htr Out") (class "Default")
      (node (ref "P19") (pin "1") (pinfunction "1_1") (pintype "passive"))
      (node (ref "Q1") (pin "2") (pinfunction "D_2") (pintype "passive"))
      (node (ref "R1") (pin "1") (pinfunction "1_1") (pintype "passive"))
    )
    (net (code "21") (name "/Conning Tower Htr_LED") (class "Default")
      (node (ref "DS1") (pin "2") (pinfunction "K_2") (pintype "passive"))
      (node (ref "R1") (pin "2") (pinfunction "2_2") (pintype "passive"))
    )
    (net (code "22") (name "/Conning Tower Thermistor") (class "Default")
      (node (ref "C14") (pin "1") (pinfunction "1_1") (pintype "passive"))
      (node (ref "R49") (pin "2") (pinfunction "2_2") (pintype "passive"))
      (node (ref "U2") (pin "22") (pinfunction "S4_22") (pintype "passive"))
    )
    (net (code "23") (name "/Cross_Black") (class "Default")
      (node (ref "P1") (pin "2") (pinfunction "2_2") (pintype "passive"))
    )
    (net (code "24") (name "/Cross_Blue") (class "Default")
      (node (ref "P1") (pin "3") (pinfunction "3_3") (pintype "passive"))
    )
    (net (code "25") (name "/Cross_Out") (class "Default")
      (node (ref "U2") (pin "11") (pinfunction "S9_11") (pintype "passive"))
    )
    (net (code "26") (name "/Cross_Yellow") (class "Default")
      (node (ref "P1") (pin "1") (pinfunction "1_1") (pintype "passive"))
    )
    (net (code "27") (name "/Gearbox Heater FET") (class "Default")
      (node (ref "P14") (pin "15") (pinfunction "15_15") (pintype "passive"))
      (node (ref "R10") (pin "1") (pinfunction "1_1") (pintype "passive"))
    )
    (net (code "28") (name "/Gearbox Htr Out") (class "Default")
      (node (ref "P18") (pin "1") (pinfunction "1_1") (pintype "passive"))
      (node (ref "Q4") (pin "2") (pinfunction "D_2") (pintype "passive"))
      (node (ref "R7") (pin "1") (pinfunction "1_1") (pintype "passive"))
    )
    (net (code "29") (name "/Gearbox Htr_LED") (class "Default")
      (node (ref "DS3") (pin "2") (pinfunction "K_2") (pintype "passive"))
      (node (ref "R7") (pin "2") (pinfunction "2_2") (pintype "passive"))
    )
    (net (code "30") (name "/Gearbox Thermistor") (class "Default")
      (node (ref "C15") (pin "1") (pinfunction "1_1") (pintype "passive"))
      (node (ref "R50") (pin "2") (pinfunction "2_2") (pintype "passive"))
      (node (ref "U2") (pin "21") (pinfunction "S3_21") (pintype "passive"))
    )
    (net (code "31") (name "/Lid Thermistor") (class "Default")
      (node (ref "C21") (pin "1") (pinfunction "1_1") (pintype "passive"))
      (node (ref "R56") (pin "2") (pinfunction "2_2") (pintype "passive"))
      (node (ref "U2") (pin "19") (pinfunction "S1_19") (pintype "passive"))
    )
    (net (code "32") (name "/Long_Black") (class "Default")
      (node (ref "P2") (pin "2") (pinfunction "2_2") (pintype "passive"))
    )
    (net (code "33") (name "/Long_Blue") (class "Default")
      (node (ref "P2") (pin "3") (pinfunction "3_3") (pintype "passive"))
    )
    (net (code "34") (name "/Long_Out") (class "Default")
      (node (ref "U2") (pin "10") (pinfunction "S10_10") (pintype "passive"))
    )
    (net (code "35") (name "/Long_Yellow") (class "Default")
      (node (ref "P2") (pin "1") (pinfunction "1_1") (pintype "passive"))
    )
    (net (code "36") (name "/MUX A2") (class "Default")
      (node (ref "P14") (pin "7") (pinfunction "7_7") (pintype "passive"))
      (node (ref "U2") (pin "15") (pinfunction "A2_15") (pintype "input"))
    )
    (net (code "37") (name "/MUX A3") (class "Default")
      (node (ref "P14") (pin "11") (pinfunction "11_11") (pintype "passive"))
      (node (ref "U2") (pin "14") (pinfunction "A3_14") (pintype "input"))
    )
    (net (code "38") (name "/MUX_A0") (class "Default")
      (node (ref "P14") (pin "8") (pinfunction "8_8") (pintype "passive"))
      (node (ref "U2") (pin "17") (pinfunction "A0_17") (pintype "input"))
    )
    (net (code "39") (name "/MUX_A1") (class "Default")
      (node (ref "P14") (pin "6") (pinfunction "6_6") (pintype "passive"))
      (node (ref "U2") (pin "16") (pinfunction "A1_16") (pintype "input"))
    )
    (net (code "40") (name "/Meter Heater FET") (class "Default")
      (node (ref "P14") (pin "13") (pinfunction "13_13") (pintype "passive"))
      (node (ref "R5") (pin "1") (pinfunction "1_1") (pintype "passive"))
    )
    (net (code "41") (name "/Meter Thermistor 1") (class "Default")
      (node (ref "C17") (pin "1") (pinfunction "1_1") (pintype "passive"))
      (node (ref "R52") (pin "2") (pinfunction "2_2") (pintype "passive"))
      (node (ref "U2") (pin "24") (pinfunction "S6_24") (pintype "passive"))
    )
    (net (code "42") (name "/Meter Thermistor 2") (class "Default")
      (node (ref "C18") (pin "1") (pinfunction "1_1") (pintype "passive"))
      (node (ref "R53") (pin "2") (pinfunction "2_2") (pintype "passive"))
      (node (ref "U2") (pin "23") (pinfunction "S5_23") (pintype "passive"))
    )
    (net (code "43") (name "/Meter_Htr_LED") (class "Default")
      (node (ref "DS2") (pin "2") (pinfunction "K_2") (pintype "passive"))
      (node (ref "R2") (pin "2") (pinfunction "2_2") (pintype "passive"))
    )
    (net (code "44") (name "/Meter_Htr_Out") (class "Default")
      (node (ref "P22") (pin "1") (pinfunction "1_1") (pintype "passive"))
      (node (ref "Q2") (pin "2") (pinfunction "D_2") (pintype "passive"))
      (node (ref "R2") (pin "1") (pinfunction "1_1") (pintype "passive"))
    )
    (net (code "45") (name "/SPI0_MISO") (class "Default")
      (node (ref "P14") (pin "9") (pinfunction "9_9") (pintype "passive"))
      (node (ref "U3") (pin "1") (pinfunction "DOUT_1") (pintype "tri_state"))
    )
    (net (code "46") (name "/SPI0_SCLK") (class "Default")
      (node (ref "P14") (pin "10") (pinfunction "10_10") (pintype "passive"))
      (node (ref "U3") (pin "10") (pinfunction "SCLK_10") (pintype "input"))
    )
    (net (code "47") (name "/Thermistor_CS0") (class "Default")
      (node (ref "P14") (pin "12") (pinfunction "12_12") (pintype "passive"))
      (node (ref "U3") (pin "9") (pinfunction "~{CS}_9") (pintype "input"))
    )
    (net (code "48") (name "GND") (class "Default")
      (node (ref "C1") (pin "1") (pinfunction "1_1") (pintype "passive"))
      (node (ref "C14") (pin "2") (pinfunction "2_2") (pintype "passive"))
      (node (ref "C15") (pin "2") (pinfunction "2_2") (pintype "passive"))
      (node (ref "C16") (pin "2") (pinfunction "2_2") (pintype "passive"))
      (node (ref "C17") (pin "2") (pinfunction "2_2") (pintype "passive"))
      (node (ref "C18") (pin "2") (pinfunction "2_2") (pintype "passive"))
      (node (ref "C19") (pin "2") (pinfunction "2_2") (pintype "passive"))
      (node (ref "C2") (pin "2") (pinfunction "2_2") (pintype "passive"))
      (node (ref "C20") (pin "2") (pinfunction "2_2") (pintype "passive"))
      (node (ref "C21") (pin "2") (pinfunction "2_2") (pintype "passive"))
      (node (ref "C3") (pin "2") (pinfunction "2_2") (pintype "passive"))
      (node (ref "C4") (pin "2") (pinfunction "2_2") (pintype "passive"))
      (node (ref "C5") (pin "2") (pinfunction "2_2") (pintype "passive"))
      (node (ref "P14") (pin "1") (pinfunction "1_1") (pintype "passive"))
      (node (ref "P14") (pin "2") (pinfunction "2_2") (pintype "passive"))
      (node (ref "P14") (pin "23") (pinfunction "23_23") (pintype "passive"))
      (node (ref "P14") (pin "24") (pinfunction "24_24") (pintype "passive"))
      (node (ref "P16") (pin "1") (pinfunction "1_1") (pintype "passive"))
      (node (ref "P17") (pin "1") (pinfunction "1_1") (pintype "passive"))
      (node (ref "P21") (pin "1") (pinfunction "1_1") (pintype "passive"))
      (node (ref "P25") (pin "1") (pinfunction "1_1") (pintype "passive"))
      (node (ref "P26") (pin "1") (pinfunction "1_1") (pintype "passive"))
      (node (ref "P27") (pin "1") (pinfunction "1_1") (pintype "passive"))
      (node (ref "P3") (pin "1") (pinfunction "1_1") (pintype "passive"))
      (node (ref "P3") (pin "3") (pinfunction "3_3") (pintype "passive"))
      (node (ref "Q1") (pin "3") (pinfunction "S_3") (pintype "passive"))
      (node (ref "Q2") (pin "3") (pinfunction "S_3") (pintype "passive"))
      (node (ref "Q3") (pin "3") (pinfunction "S_3") (pintype "passive"))
      (node (ref "Q5") (pin "3") (pinfunction "S_3") (pintype "passive"))
      (node (ref "U1") (pin "2") (pinfunction "GND_2") (pintype "passive"))
      (node (ref "U2") (pin "12") (pinfunction "GND_12") (pintype "power_in"))
      (node (ref "U2") (pin "27") (pinfunction "VSS_27") (pintype "power_in"))
      (node (ref "U3") (pin "2") (pinfunction "DGND_2") (pintype "power_in"))
      (node (ref "U3") (pin "4") (pinfunction "AGND_4") (pintype "power_in"))
      (node (ref "U3") (pin "8") (pinfunction "AGND_8") (pintype "power_in"))
    )
    (net (code "49") (name "Net-(P3-Pad2)") (class "Default")
      (node (ref "P3") (pin "2") (pinfunction "2_2") (pintype "passive"))
      (node (ref "R15") (pin "1") (pinfunction "1_1") (pintype "passive"))
      (node (ref "R53") (pin "1") (pinfunction "1_1") (pintype "passive"))
    )
    (net (code "50") (name "Net-(P3-Pad4)") (class "Default")
      (node (ref "P3") (pin "4") (pinfunction "4_4") (pintype "passive"))
      (node (ref "R14") (pin "1") (pinfunction "1_1") (pintype "passive"))
      (node (ref "R52") (pin "1") (pinfunction "1_1") (pintype "passive"))
    )
    (net (code "51") (name "Net-(P16-Pad2)") (class "Default")
      (node (ref "P16") (pin "2") (pinfunction "2_2") (pintype "passive"))
      (node (ref "R3") (pin "1") (pinfunction "1_1") (pintype "passive"))
      (node (ref "R49") (pin "1") (pinfunction "1_1") (pintype "passive"))
    )
    (net (code "52") (name "Net-(P17-Pad2)") (class "Default")
      (node (ref "P17") (pin "2") (pinfunction "2_2") (pintype "passive"))
      (node (ref "R50") (pin "1") (pinfunction "1_1") (pintype "passive"))
      (node (ref "R6") (pin "1") (pinfunction "1_1") (pintype "passive"))
    )
    (net (code "53") (name "Net-(P21-Pad2)") (class "Default")
      (node (ref "P21") (pin "2") (pinfunction "2_2") (pintype "passive"))
      (node (ref "R11") (pin "1") (pinfunction "1_1") (pintype "passive"))
      (node (ref "R51") (pin "1") (pinfunction "1_1") (pintype "passive"))
    )
    (net (code "54") (name "Net-(P25-Pad2)") (class "Default")
      (node (ref "P25") (pin "2") (pinfunction "2_2") (pintype "passive"))
      (node (ref "R18") (pin "1") (pinfunction "1_1") (pintype "passive"))
      (node (ref "R54") (pin "1") (pinfunction "1_1") (pintype "passive"))
    )
    (net (code "55") (name "Net-(P26-Pad2)") (class "Default")
      (node (ref "P26") (pin "2") (pinfunction "2_2") (pintype "passive"))
      (node (ref "R19") (pin "1") (pinfunction "1_1") (pintype "passive"))
      (node (ref "R55") (pin "1") (pinfunction "1_1") (pintype "passive"))
    )
    (net (code "56") (name "Net-(P27-Pad2)") (class "Default")
      (node (ref "P27") (pin "2") (pinfunction "2_2") (pintype "passive"))
      (node (ref "R20") (pin "1") (pinfunction "1_1") (pintype "passive"))
      (node (ref "R56") (pin "1") (pinfunction "1_1") (pintype "passive"))
    )
    (net (code "57") (name "Net-(Q1-G)") (class "Default")
      (node (ref "Q1") (pin "1") (pinfunction "G_1") (pintype "passive"))
      (node (ref "R4") (pin "2") (pinfunction "2_2") (pintype "passive"))
    )
    (net (code "58") (name "Net-(Q2-G)") (class "Default")
      (node (ref "Q2") (pin "1") (pinfunction "G_1") (pintype "passive"))
      (node (ref "R5") (pin "2") (pinfunction "2_2") (pintype "passive"))
    )
    (net (code "59") (name "Net-(Q3-G)") (class "Default")
      (node (ref "Q3") (pin "1") (pinfunction "G_1") (pintype "passive"))
      (node (ref "R9") (pin "2") (pinfunction "2_2") (pintype "passive"))
    )
    (net (code "60") (name "Net-(Q4-G)") (class "Default")
      (node (ref "Q4") (pin "1") (pinfunction "G_1") (pintype "passive"))
      (node (ref "R10") (pin "2") (pinfunction "2_2") (pintype "passive"))
    )
    (net (code "61") (name "Net-(Q5-G)") (class "Default")
      (node (ref "Q5") (pin "1") (pinfunction "G_1") (pintype "passive"))
      (node (ref "R16") (pin "2") (pinfunction "2_2") (pintype "passive"))
    )
    (net (code "62") (name "Net-(Q6-G)") (class "Default")
      (node (ref "Q6") (pin "1") (pinfunction "G_1") (pintype "passive"))
      (node (ref "R17") (pin "2") (pinfunction "2_2") (pintype "passive"))
    )
    (net (code "63") (name "Net-(U1-Filter)") (class "Default")
      (node (ref "C1") (pin "2") (pinfunction "2_2") (pintype "passive"))
      (node (ref "U1") (pin "1") (pinfunction "Filter_1") (pintype "passive"))
    )
    (net (code "64") (name "unconnected-(P1-Pad4)") (class "Default")
      (node (ref "P1") (pin "4") (pinfunction "4_4") (pintype "passive+no_connect"))
    )
    (net (code "65") (name "unconnected-(P2-Pad4)") (class "Default")
      (node (ref "P2") (pin "4") (pinfunction "4_4") (pintype "passive+no_connect"))
    )
    (net (code "66") (name "unconnected-(P14-Pad4)") (class "Default")
      (node (ref "P14") (pin "4") (pinfunction "4_4") (pintype "passive+no_connect"))
    )
    (net (code "67") (name "unconnected-(P14-Pad5)") (class "Default")
      (node (ref "P14") (pin "5") (pinfunction "5_5") (pintype "passive+no_connect"))
    )
    (net (code "68") (name "unconnected-(Q4-S-Pad3)") (class "Default")
      (node (ref "Q4") (pin "3") (pinfunction "S_3") (pintype "passive"))
    )
    (net (code "69") (name "unconnected-(Q6-S-Pad3)") (class "Default")
      (node (ref "Q6") (pin "3") (pinfunction "S_3") (pintype "passive"))
    )
    (net (code "70") (name "unconnected-(U2-NC-Pad2)") (class "Default")
      (node (ref "U2") (pin "2") (pinfunction "NC_2") (pintype "passive"))
    )
    (net (code "71") (name "unconnected-(U2-NC-Pad3)") (class "Default")
      (node (ref "U2") (pin "3") (pinfunction "NC_3") (pintype "passive"))
    )
    (net (code "72") (name "unconnected-(U2-NC-Pad13)") (class "Default")
      (node (ref "U2") (pin "13") (pinfunction "NC_13") (pintype "passive"))
    )
    (net (code "73") (name "unconnected-(U2-S11-Pad9)") (class "Default")
      (node (ref "U2") (pin "9") (pinfunction "S11_9") (pintype "passive"))
    )
    (net (code "74") (name "unconnected-(U2-S12-Pad8)") (class "Default")
      (node (ref "U2") (pin "8") (pinfunction "S12_8") (pintype "passive"))
    )
    (net (code "75") (name "unconnected-(U2-S13-Pad7)") (class "Default")
      (node (ref "U2") (pin "7") (pinfunction "S13_7") (pintype "passive"))
    )
    (net (code "76") (name "unconnected-(U2-S14-Pad6)") (class "Default")
      (node (ref "U2") (pin "6") (pinfunction "S14_6") (pintype "passive"))
    )
    (net (code "77") (name "unconnected-(U2-S15-Pad5)") (class "Default")
      (node (ref "U2") (pin "5") (pinfunction "S15_5") (pintype "passive"))
    )
    (net (code "78") (name "unconnected-(U2-S16-Pad4)") (class "Default")
      (node (ref "U2") (pin "4") (pinfunction "S16_4") (pintype "passive"))
    )
  )
)
